# mp4560_ps.net
KiCad netlist of a schematic drawn in EAGLE
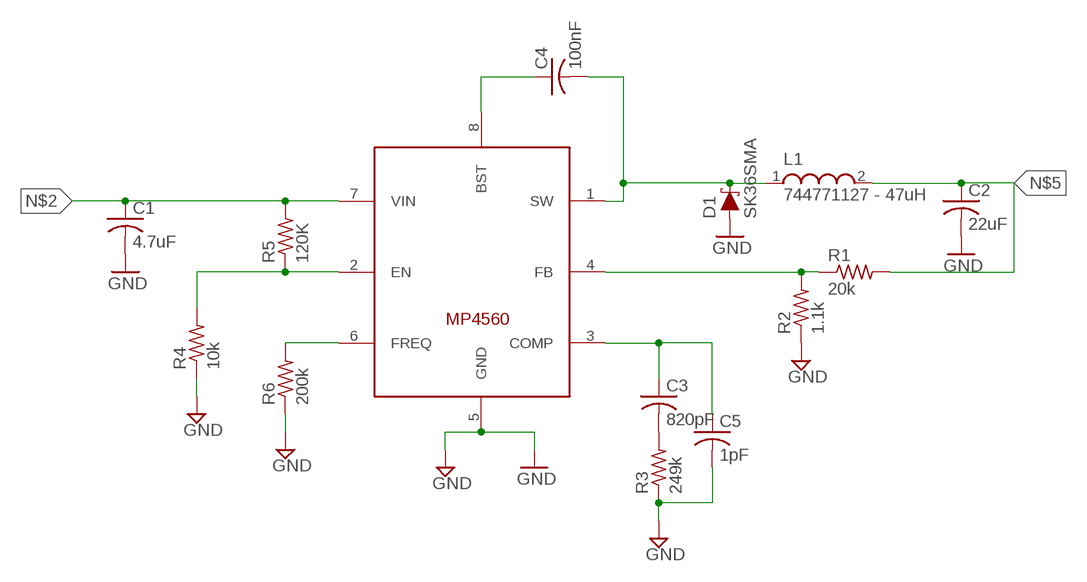
[diagram p0: schematic, sheet 1]

(export (version "E")
  (design (tool "Eeschema 10.0.6"))
  (components
    (comp (ref "C1")
      (value "4.7uF")
      (footprint "eagle-import:C1210")
      (libsource (lib "eagle-import") (part "C-USC1210"))
    )
    (comp (ref "C2")
      (value "22uF")
      (footprint "eagle-import:C1210")
      (libsource (lib "eagle-import") (part "C-USC1210"))
    )
    (comp (ref "C3")
      (value "820pF")
      (footprint "eagle-import:C0805")
      (libsource (lib "eagle-import") (part "C-USC0805"))
    )
    (comp (ref "C4")
      (value "100nF")
      (footprint "eagle-import:C0805")
      (libsource (lib "eagle-import") (part "C-USC0805"))
    )
    (comp (ref "C5")
      (value "1pF")
      (footprint "eagle-import:C0805")
      (libsource (lib "eagle-import") (part "C-USC0805"))
    )
    (comp (ref "D1")
      (value "SK36SMA")
      (footprint "eagle-import:SMA-DIODE")
      (libsource (lib "eagle-import") (part "DIODE-SCHOTTKY-B340A"))
    )
    (comp (ref "L1")
      (value "744771127 - 47uH")
      (footprint "eagle-import:WE-PD_1260_1245_1280_1210")
      (libsource (lib "eagle-import") (part "WE-PD_1260/1245/1280/1210"))
    )
    (comp (ref "R1")
      (value "20k")
      (footprint "eagle-import:R0805")
      (libsource (lib "eagle-import") (part "R-US_R0805"))
    )
    (comp (ref "R2")
      (value "1.1k")
      (footprint "eagle-import:R0805")
      (libsource (lib "eagle-import") (part "R-US_R0805"))
    )
    (comp (ref "R3")
      (value "249k")
      (footprint "eagle-import:R0805")
      (libsource (lib "eagle-import") (part "R-US_R0805"))
    )
    (comp (ref "R4")
      (value "10k")
      (footprint "eagle-import:R0805")
      (libsource (lib "eagle-import") (part "R-US_R0805"))
    )
    (comp (ref "R5")
      (value "120K")
      (footprint "eagle-import:R0805")
      (libsource (lib "eagle-import") (part "R-US_R0805"))
    )
    (comp (ref "R6")
      (value "200k")
      (footprint "eagle-import:R0805")
      (libsource (lib "eagle-import") (part "R-US_R0805"))
    )
    (comp (ref "U$1")
      (value "MP4560")
      (footprint "eagle-import:SOIC8")
      (libsource (lib "eagle-import") (part "MP4560"))
    )
  )
  (nets
    (net (code "1") (name "GND") (class "Default")
      (node (ref "C1") (pin "2") (pinfunction "2_2") (pintype "passive"))
      (node (ref "C2") (pin "2") (pinfunction "2_2") (pintype "passive"))
      (node (ref "C5") (pin "2") (pinfunction "2_2") (pintype "passive"))
      (node (ref "D1") (pin "A") (pinfunction "A_A") (pintype "passive"))
      (node (ref "R2") (pin "1") (pinfunction "1_1") (pintype "passive"))
      (node (ref "R3") (pin "1") (pinfunction "1_1") (pintype "passive"))
      (node (ref "R4") (pin "1") (pinfunction "1_1") (pintype "passive"))
      (node (ref "R6") (pin "1") (pinfunction "1_1") (pintype "passive"))
      (node (ref "U$1") (pin "5") (pinfunction "GND_5") (pintype "bidirectional"))
    )
    (net (code "2") (name "N$2") (class "Default")
      (node (ref "C1") (pin "1") (pinfunction "1_1") (pintype "passive"))
      (node (ref "R5") (pin "2") (pinfunction "2_2") (pintype "passive"))
      (node (ref "U$1") (pin "7") (pinfunction "VIN_7") (pintype "bidirectional"))
    )
    (net (code "3") (name "N$5") (class "Default")
      (node (ref "C2") (pin "1") (pinfunction "1_1") (pintype "passive"))
      (node (ref "L1") (pin "2") (pinfunction "2_2") (pintype "passive"))
      (node (ref "R1") (pin "2") (pinfunction "2_2") (pintype "passive"))
    )
    (net (code "4") (name "Net-(C3-Pad2)") (class "Default")
      (node (ref "C3") (pin "2") (pinfunction "2_2") (pintype "passive"))
      (node (ref "R3") (pin "2") (pinfunction "2_2") (pintype "passive"))
    )
    (net (code "5") (name "Net-(U$1-BST)") (class "Default")
      (node (ref "C4") (pin "1") (pinfunction "1_1") (pintype "passive"))
      (node (ref "U$1") (pin "8") (pinfunction "BST_8") (pintype "bidirectional"))
    )
    (net (code "6") (name "Net-(U$1-COMP)") (class "Default")
      (node (ref "C3") (pin "1") (pinfunction "1_1") (pintype "passive"))
      (node (ref "C5") (pin "1") (pinfunction "1_1") (pintype "passive"))
      (node (ref "U$1") (pin "3") (pinfunction "COMP_3") (pintype "bidirectional"))
    )
    (net (code "7") (name "Net-(U$1-EN)") (class "Default")
      (node (ref "R4") (pin "2") (pinfunction "2_2") (pintype "passive"))
      (node (ref "R5") (pin "1") (pinfunction "1_1") (pintype "passive"))
      (node (ref "U$1") (pin "2") (pinfunction "EN_2") (pintype "bidirectional"))
    )
    (net (code "8") (name "Net-(U$1-FB)") (class "Default")
      (node (ref "R1") (pin "1") (pinfunction "1_1") (pintype "passive"))
      (node (ref "R2") (pin "2") (pinfunction "2_2") (pintype "passive"))
      (node (ref "U$1") (pin "4") (pinfunction "FB_4") (pintype "bidirectional"))
    )
    (net (code "9") (name "Net-(U$1-FREQ)") (class "Default")
      (node (ref "R6") (pin "2") (pinfunction "2_2") (pintype "passive"))
      (node (ref "U$1") (pin "6") (pinfunction "FREQ_6") (pintype "bidirectional"))
    )
    (net (code "10") (name "Net-(U$1-SW)") (class "Default")
      (node (ref "C4") (pin "2") (pinfunction "2_2") (pintype "passive"))
      (node (ref "D1") (pin "C") (pinfunction "C_C") (pintype "passive"))
      (node (ref "L1") (pin "1") (pinfunction "1_1") (pintype "passive"))
      (node (ref "U$1") (pin "1") (pinfunction "SW_1") (pintype "bidirectional"))
    )
  )
)
